# Ex_Alligator.net
KiCad netlist of a schematic drawn in EAGLE
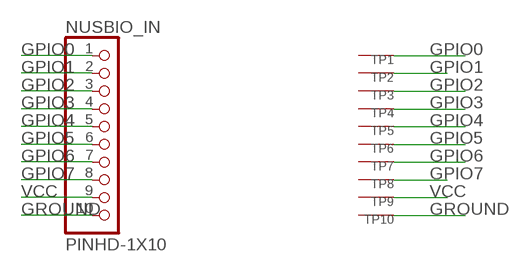
[diagram p0: schematic, sheet 1]

(export (version "E")
  (design (tool "Eeschema 10.0.6"))
  (components
    (comp (ref "NUSBIO_IN")
      (value "PINHD-1X10")
      (footprint "eagle-import:1X10-BIG")
      (libsource (lib "eagle-import") (part "PINHD-1X10"))
    )
    (comp (ref "TP1")
      (value "SEWTAPBIG")
      (footprint "eagle-import:BIGTAP")
      (libsource (lib "eagle-import") (part "SEWTAPBIG"))
    )
    (comp (ref "TP2")
      (value "SEWTAPBIG")
      (footprint "eagle-import:BIGTAP")
      (libsource (lib "eagle-import") (part "SEWTAPBIG"))
    )
    (comp (ref "TP3")
      (value "SEWTAPBIG")
      (footprint "eagle-import:BIGTAP")
      (libsource (lib "eagle-import") (part "SEWTAPBIG"))
    )
    (comp (ref "TP4")
      (value "SEWTAPBIG")
      (footprint "eagle-import:BIGTAP")
      (libsource (lib "eagle-import") (part "SEWTAPBIG"))
    )
    (comp (ref "TP5")
      (value "SEWTAPBIG")
      (footprint "eagle-import:BIGTAP")
      (libsource (lib "eagle-import") (part "SEWTAPBIG"))
    )
    (comp (ref "TP6")
      (value "SEWTAPBIG")
      (footprint "eagle-import:BIGTAP")
      (libsource (lib "eagle-import") (part "SEWTAPBIG"))
    )
    (comp (ref "TP7")
      (value "SEWTAPBIG")
      (footprint "eagle-import:BIGTAP")
      (libsource (lib "eagle-import") (part "SEWTAPBIG"))
    )
    (comp (ref "TP8")
      (value "SEWTAPBIG")
      (footprint "eagle-import:BIGTAP")
      (libsource (lib "eagle-import") (part "SEWTAPBIG"))
    )
    (comp (ref "TP9")
      (value "SEWTAPBIG")
      (footprint "eagle-import:BIGTAP")
      (libsource (lib "eagle-import") (part "SEWTAPBIG"))
    )
    (comp (ref "TP10")
      (value "SEWTAPBIG")
      (footprint "eagle-import:BIGTAP")
      (libsource (lib "eagle-import") (part "SEWTAPBIG"))
    )
  )
  (nets
    (net (code "1") (name "/GPIO0") (class "Default")
      (node (ref "NUSBIO_IN") (pin "1") (pinfunction "1_1") (pintype "passive"))
      (node (ref "TP1") (pin "P$1") (pinfunction "SEW_P$1") (pintype "bidirectional"))
    )
    (net (code "2") (name "/GPIO1") (class "Default")
      (node (ref "NUSBIO_IN") (pin "2") (pinfunction "2_2") (pintype "passive"))
      (node (ref "TP2") (pin "P$1") (pinfunction "SEW_P$1") (pintype "bidirectional"))
    )
    (net (code "3") (name "/GPIO2") (class "Default")
      (node (ref "NUSBIO_IN") (pin "3") (pinfunction "3_3") (pintype "passive"))
      (node (ref "TP3") (pin "P$1") (pinfunction "SEW_P$1") (pintype "bidirectional"))
    )
    (net (code "4") (name "/GPIO3") (class "Default")
      (node (ref "NUSBIO_IN") (pin "4") (pinfunction "4_4") (pintype "passive"))
      (node (ref "TP4") (pin "P$1") (pinfunction "SEW_P$1") (pintype "bidirectional"))
    )
    (net (code "5") (name "/GPIO4") (class "Default")
      (node (ref "NUSBIO_IN") (pin "5") (pinfunction "5_5") (pintype "passive"))
      (node (ref "TP5") (pin "P$1") (pinfunction "SEW_P$1") (pintype "bidirectional"))
    )
    (net (code "6") (name "/GPIO5") (class "Default")
      (node (ref "NUSBIO_IN") (pin "6") (pinfunction "6_6") (pintype "passive"))
      (node (ref "TP6") (pin "P$1") (pinfunction "SEW_P$1") (pintype "bidirectional"))
    )
    (net (code "7") (name "/GPIO6") (class "Default")
      (node (ref "NUSBIO_IN") (pin "7") (pinfunction "7_7") (pintype "passive"))
      (node (ref "TP7") (pin "P$1") (pinfunction "SEW_P$1") (pintype "bidirectional"))
    )
    (net (code "8") (name "/GPIO7") (class "Default")
      (node (ref "NUSBIO_IN") (pin "8") (pinfunction "8_8") (pintype "passive"))
      (node (ref "TP8") (pin "P$1") (pinfunction "SEW_P$1") (pintype "bidirectional"))
    )
    (net (code "9") (name "/GROUND") (class "Default")
      (node (ref "NUSBIO_IN") (pin "10") (pinfunction "10_10") (pintype "passive"))
      (node (ref "TP10") (pin "P$1") (pinfunction "SEW_P$1") (pintype "bidirectional"))
    )
    (net (code "10") (name "/VCC") (class "Default")
      (node (ref "NUSBIO_IN") (pin "9") (pinfunction "9_9") (pintype "passive"))
      (node (ref "TP9") (pin "P$1") (pinfunction "SEW_P$1") (pintype "bidirectional"))
    )
  )
)
